# LinearRegulator.net
KiCad netlist of a schematic drawn in EAGLE
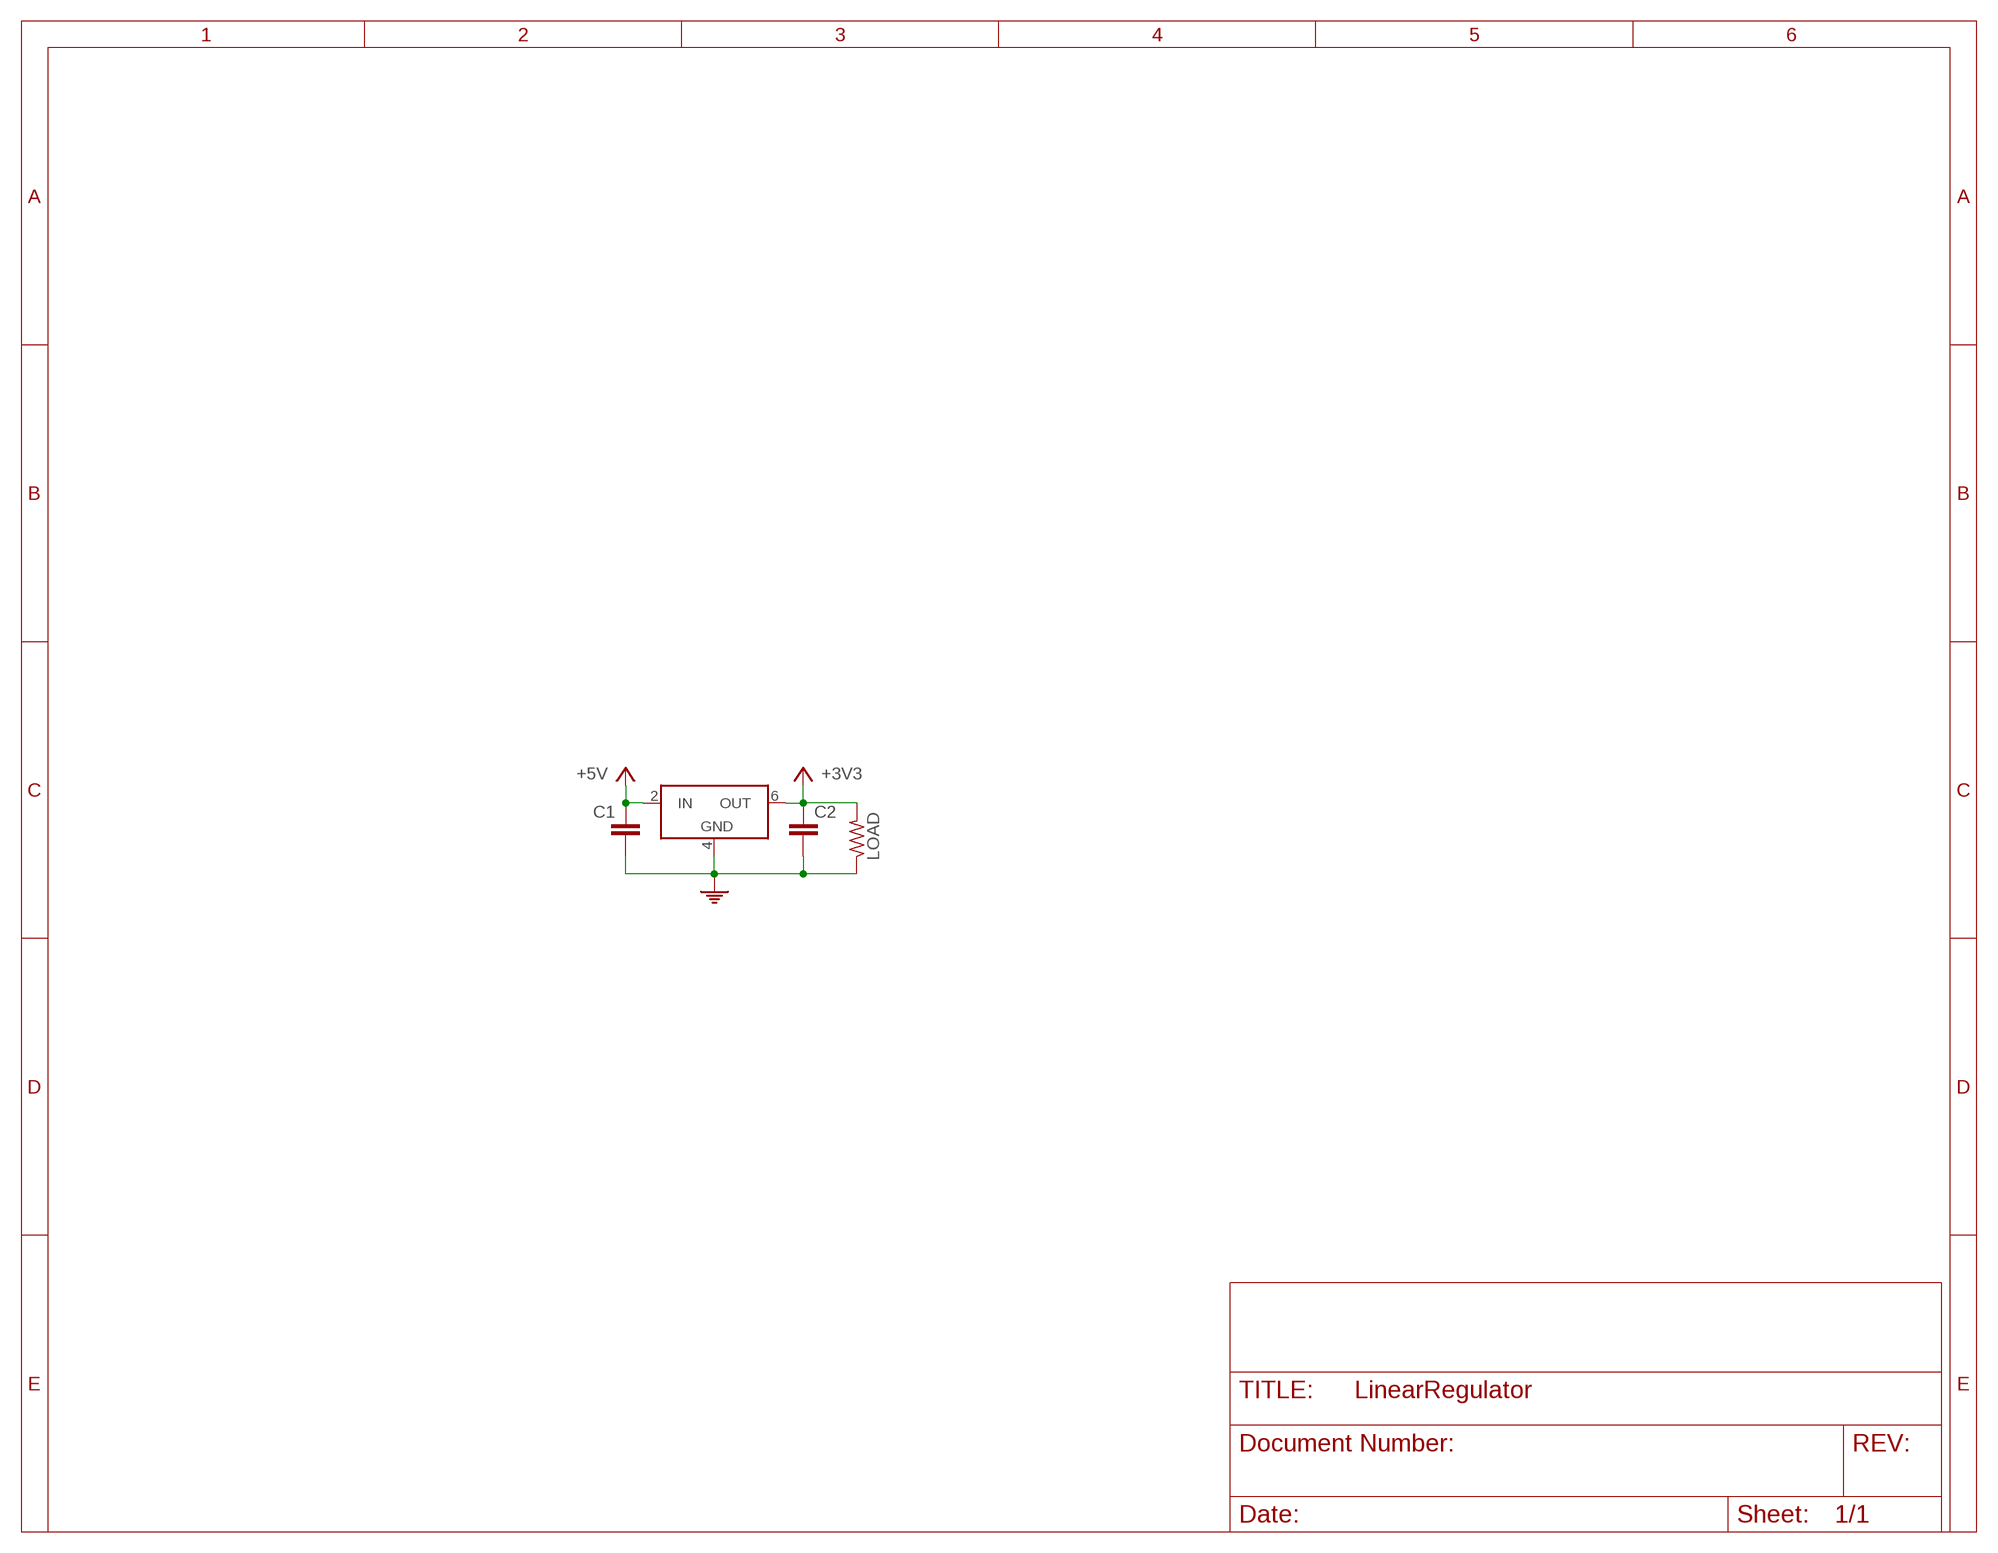
[diagram p0: schematic, sheet 1]

(export (version "E")
  (design (tool "Eeschema 10.0.6"))
  (components
    (comp (ref "C1")
      (value "C2,5-3")
      (footprint "eagle-import:C2.5-3")
      (libsource (lib "eagle-import") (part "C2,5-3"))
    )
    (comp (ref "C2")
      (value "C2,5-3")
      (footprint "eagle-import:C2.5-3")
      (libsource (lib "eagle-import") (part "C2,5-3"))
    )
    (comp (ref "IC1")
      (value "LT1021N")
      (footprint "eagle-import:DIL08")
      (fields (field (name "MPN") "LT1021BCN8-5#PBF"))
      (libsource (lib "eagle-import") (part "LT1021N"))
    )
    (comp (ref "LOAD")
      (value "R-US_0204/2V")
      (footprint "eagle-import:0204V")
      (libsource (lib "eagle-import") (part "R-US_0204/2V"))
    )
  )
  (nets
    (net (code "1") (name "+3V3") (class "Default")
      (node (ref "C2") (pin "1") (pinfunction "1_1") (pintype "passive"))
      (node (ref "IC1") (pin "6") (pinfunction "OUT_6") (pintype "output"))
      (node (ref "LOAD") (pin "2") (pinfunction "2_2") (pintype "passive"))
    )
    (net (code "2") (name "+5V") (class "Default")
      (node (ref "C1") (pin "1") (pinfunction "1_1") (pintype "passive"))
      (node (ref "IC1") (pin "2") (pinfunction "IN_2") (pintype "input"))
    )
    (net (code "3") (name "PE") (class "Default")
      (node (ref "C1") (pin "2") (pinfunction "2_2") (pintype "passive"))
      (node (ref "C2") (pin "2") (pinfunction "2_2") (pintype "passive"))
      (node (ref "IC1") (pin "4") (pinfunction "GND_4") (pintype "power_in"))
      (node (ref "LOAD") (pin "1") (pinfunction "1_1") (pintype "passive"))
    )
  )
)
